# esp32-thing.net
KiCad netlist of a schematic drawn in EAGLE
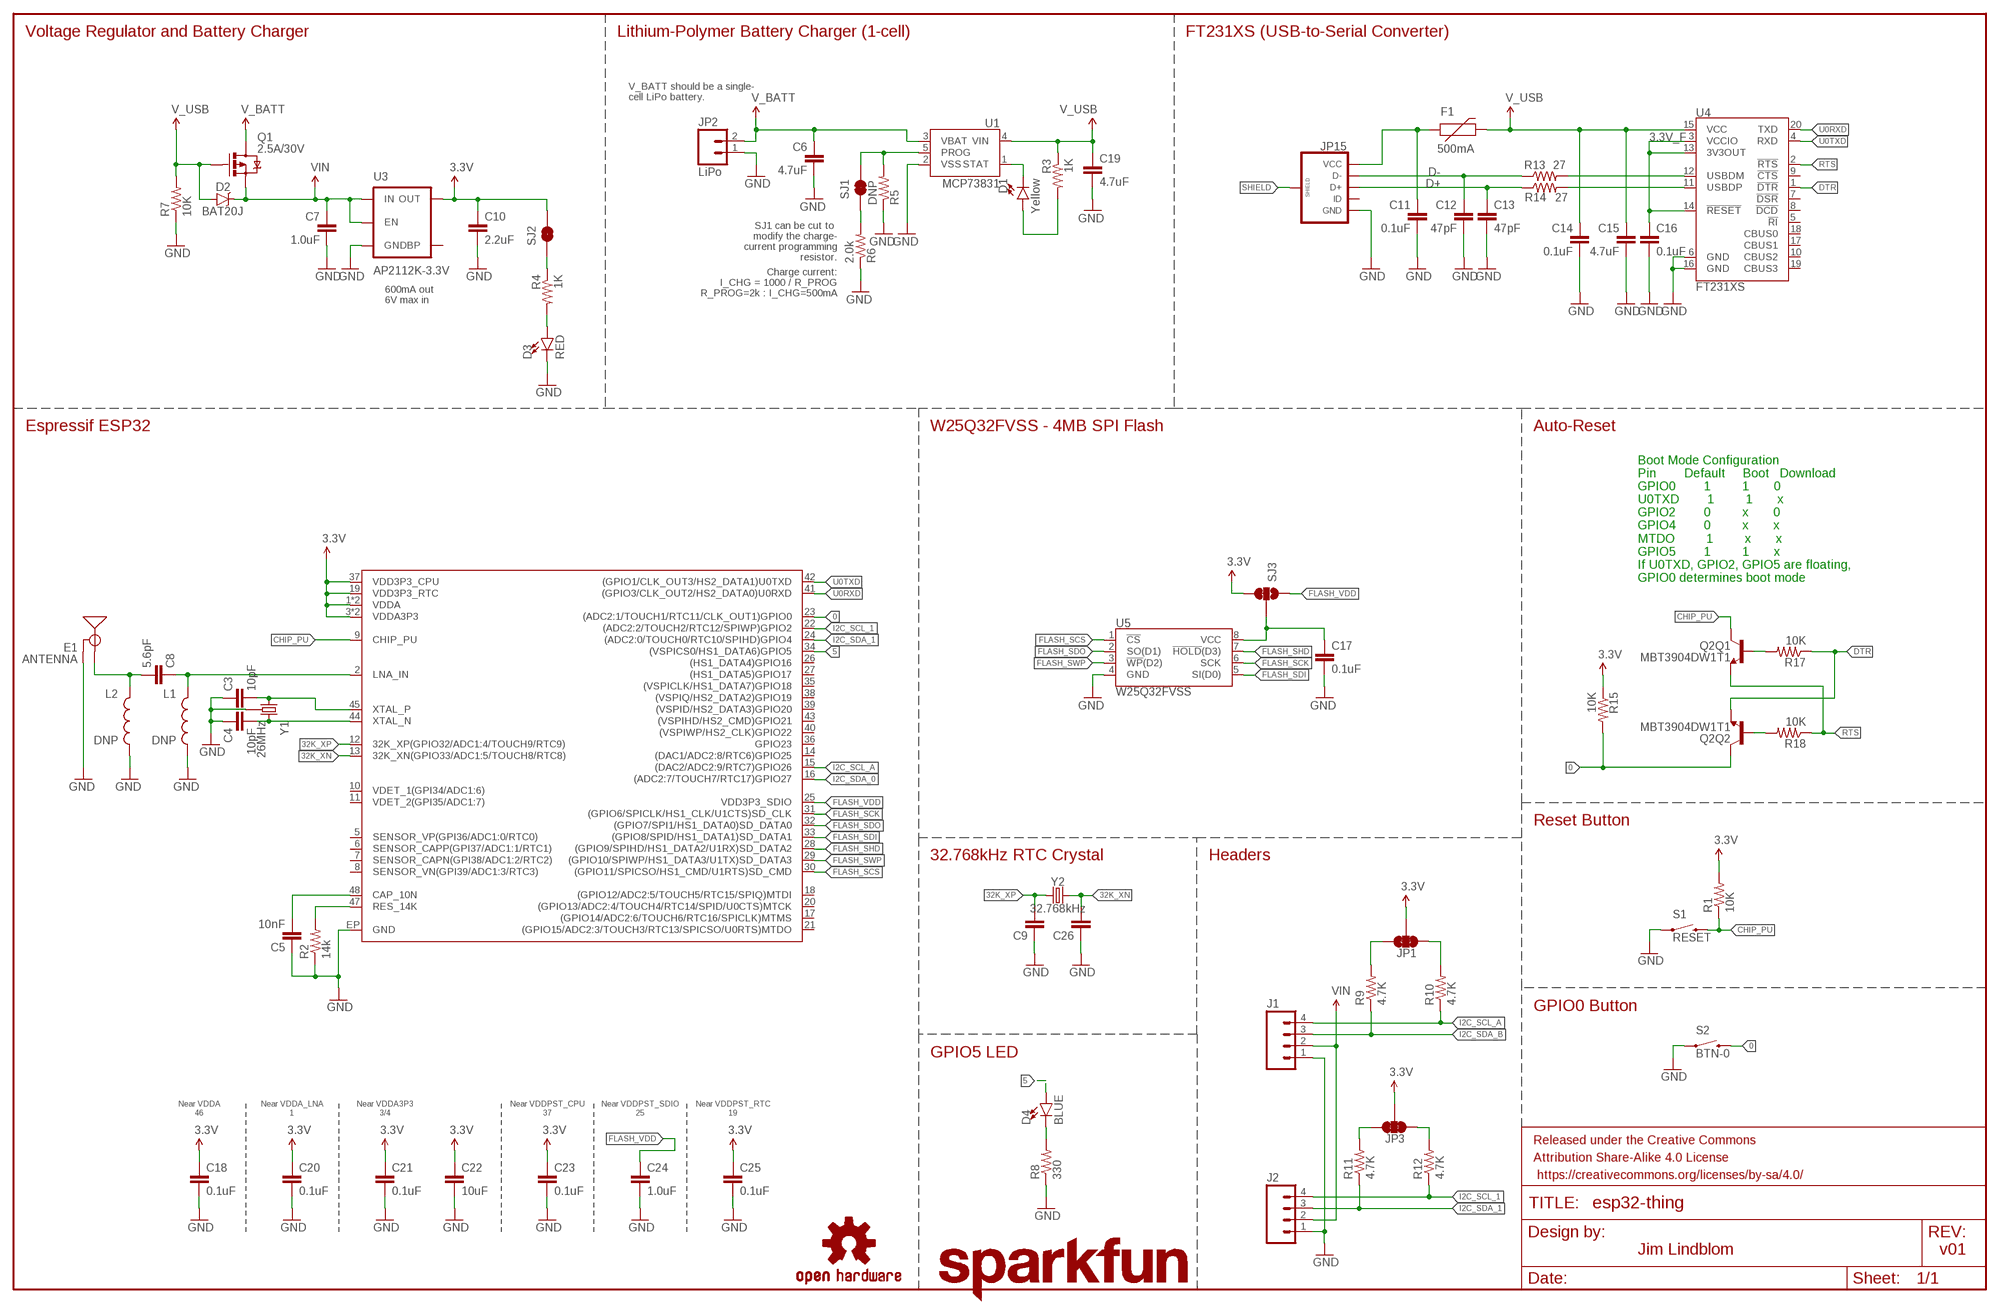
[diagram p0: schematic, sheet 1]

(export (version "E")
  (design (tool "Eeschema 10.0.6"))
  (components
    (comp (ref "C3")
      (value "10pF")
      (footprint "eagle-import:0603-CAP")
      (libsource (lib "eagle-import") (part "10PF-50V-5%(0603)"))
    )
    (comp (ref "C4")
      (value "10pF")
      (footprint "eagle-import:0603-CAP")
      (libsource (lib "eagle-import") (part "10PF-50V-5%(0603)"))
    )
    (comp (ref "C5")
      (value "10nF")
      (footprint "eagle-import:0603-CAP")
      (libsource (lib "eagle-import") (part "10NF/10000PF-50V-10%(0603)"))
    )
    (comp (ref "C6")
      (value "4.7uF")
      (footprint "eagle-import:0603-CAP")
      (libsource (lib "eagle-import") (part "4.7UF-6.3V-10%(0603)0603"))
    )
    (comp (ref "C7")
      (value "1.0uF")
      (footprint "eagle-import:0805-CAP")
      (libsource (lib "eagle-import") (part "1.0UF-25V-+80/-20(0805){dblquote}"))
    )
    (comp (ref "C8")
      (value "5.6pF")
      (footprint "eagle-import:0603-CAP")
      (libsource (lib "eagle-import") (part "CAP0603-CAP"))
    )
    (comp (ref "C9")
      (value "CAP0603-CAP")
      (footprint "eagle-import:0603-CAP")
      (libsource (lib "eagle-import") (part "SparkFun-Passives_CAP0603-CAP"))
    )
    (comp (ref "C10")
      (value "2.2uF")
      (footprint "eagle-import:0603-CAP")
      (libsource (lib "eagle-import") (part "2.2UF-10V-20%(0603)"))
    )
    (comp (ref "C11")
      (value "0.1uF")
      (footprint "eagle-import:0603-CAP")
      (libsource (lib "eagle-import") (part "0.1UF-25V(+80/-20%)(0603)"))
    )
    (comp (ref "C12")
      (value "47pF")
      (footprint "eagle-import:0603-CAP")
      (libsource (lib "eagle-import") (part "47PF-50V-5%(0603)"))
    )
    (comp (ref "C13")
      (value "47pF")
      (footprint "eagle-import:0603-CAP")
      (libsource (lib "eagle-import") (part "47PF-50V-5%(0603)"))
    )
    (comp (ref "C14")
      (value "0.1uF")
      (footprint "eagle-import:0603-CAP")
      (libsource (lib "eagle-import") (part "0.1UF-25V(+80/-20%)(0603)"))
    )
    (comp (ref "C15")
      (value "4.7uF")
      (footprint "eagle-import:0603-CAP")
      (libsource (lib "eagle-import") (part "4.7UF-6.3V-10%(0603)0603"))
    )
    (comp (ref "C16")
      (value "0.1uF")
      (footprint "eagle-import:0603-CAP")
      (libsource (lib "eagle-import") (part "0.1UF-25V(+80/-20%)(0603)"))
    )
    (comp (ref "C17")
      (value "0.1uF")
      (footprint "eagle-import:0603-CAP")
      (libsource (lib "eagle-import") (part "0.1UF-25V(+80/-20%)(0603)"))
    )
    (comp (ref "C18")
      (value "0.1uF")
      (footprint "eagle-import:0603-CAP")
      (libsource (lib "eagle-import") (part "0.1UF-25V(+80/-20%)(0603)"))
    )
    (comp (ref "C19")
      (value "4.7uF")
      (footprint "eagle-import:0603-CAP")
      (libsource (lib "eagle-import") (part "4.7UF-6.3V-10%(0603)0603"))
    )
    (comp (ref "C20")
      (value "0.1uF")
      (footprint "eagle-import:0603-CAP")
      (libsource (lib "eagle-import") (part "0.1UF-25V(+80/-20%)(0603)"))
    )
    (comp (ref "C21")
      (value "0.1uF")
      (footprint "eagle-import:0603-CAP")
      (libsource (lib "eagle-import") (part "0.1UF-25V(+80/-20%)(0603)"))
    )
    (comp (ref "C22")
      (value "10uF")
      (footprint "eagle-import:0603-CAP")
      (libsource (lib "eagle-import") (part "10UF-6.3V-20%(0603)"))
    )
    (comp (ref "C23")
      (value "0.1uF")
      (footprint "eagle-import:0603-CAP")
      (libsource (lib "eagle-import") (part "0.1UF-25V(+80/-20%)(0603)"))
    )
    (comp (ref "C24")
      (value "1.0uF")
      (footprint "eagle-import:0603-CAP")
      (libsource (lib "eagle-import") (part "1.0UF-16V-10%(0603)"))
    )
    (comp (ref "C25")
      (value "0.1uF")
      (footprint "eagle-import:0603-CAP")
      (libsource (lib "eagle-import") (part "0.1UF-25V(+80/-20%)(0603)"))
    )
    (comp (ref "C26")
      (value "CAP0603-CAP")
      (footprint "eagle-import:0603-CAP")
      (libsource (lib "eagle-import") (part "SparkFun-Passives_CAP0603-CAP"))
    )
    (comp (ref "D1")
      (value "Yellow")
      (footprint "eagle-import:LED-0603")
      (libsource (lib "eagle-import") (part "LED-YELLOW0603"))
    )
    (comp (ref "D2")
      (value "BAT20J")
      (footprint "eagle-import:SOD-323")
      (libsource (lib "eagle-import") (part "DIODE-SCHOTTKY-BAT20J"))
    )
    (comp (ref "D3")
      (value "RED")
      (footprint "eagle-import:LED-0603")
      (libsource (lib "eagle-import") (part "LED-RED0603"))
    )
    (comp (ref "D4")
      (value "BLUE")
      (footprint "eagle-import:LED-0603")
      (libsource (lib "eagle-import") (part "LED-BLUE0603"))
    )
    (comp (ref "E1")
      (value "ANTENNA")
      (footprint "eagle-import:TRACE_ANTENNA_2.4GHZ_25.7MM_TUNED")
      (libsource (lib "eagle-import") (part "ANTENNATRACE-TUNED"))
    )
    (comp (ref "F1")
      (value "500mA")
      (footprint "eagle-import:PTC-1206")
      (libsource (lib "eagle-import") (part "PTCSMD"))
    )
    (comp (ref "FRAME1")
      (value "FRAME-LEDGER")
      (footprint "eagle-import:CREATIVE_COMMONS")
      (libsource (lib "eagle-import") (part "FRAME-LEDGER"))
    )
    (comp (ref "J1")
      (value "M04POLAR_LOCK")
      (footprint "eagle-import:MOLEX-1X4_LOCK")
      (libsource (lib "eagle-import") (part "M04POLAR_LOCK"))
    )
    (comp (ref "J2")
      (value "M04POLAR_LOCK")
      (footprint "eagle-import:MOLEX-1X4_LOCK")
      (libsource (lib "eagle-import") (part "M04POLAR_LOCK"))
    )
    (comp (ref "JP1")
      (value "JUMPER-PAD-3-NC_BY_TRACE")
      (footprint "eagle-import:PAD-JUMPER-3-3OF3_NC_BY_TRACE_YES_SILK_FULL_BOX")
      (libsource (lib "eagle-import") (part "JUMPER-PAD-3-NC_BY_TRACE"))
    )
    (comp (ref "JP2")
      (value "LiPo")
      (footprint "eagle-import:JST-2-PTH")
      (libsource (lib "eagle-import") (part "M02JST-PTH-2"))
    )
    (comp (ref "JP3")
      (value "JUMPER-PAD-3-NC_BY_TRACE")
      (footprint "eagle-import:PAD-JUMPER-3-3OF3_NC_BY_TRACE_YES_SILK_FULL_BOX")
      (libsource (lib "eagle-import") (part "JUMPER-PAD-3-NC_BY_TRACE"))
    )
    (comp (ref "JP15")
      (value "USB_MICROB_PLUGCONN-11752")
      (footprint "eagle-import:USB-B-MICRO-SMD_V03")
      (libsource (lib "eagle-import") (part "USB_MICROB_PLUGCONN-11752"))
    )
    (comp (ref "L1")
      (value "DNP")
      (footprint "eagle-import:0603")
      (libsource (lib "eagle-import") (part "INDUCTOR0603"))
    )
    (comp (ref "L2")
      (value "DNP")
      (footprint "eagle-import:0603")
      (libsource (lib "eagle-import") (part "INDUCTOR0603"))
    )
    (comp (ref "LOGO1")
      (value "SFE_LOGO_NAME.2_INCH")
      (footprint "eagle-import:SFE_LOGO_NAME_.2")
      (libsource (lib "eagle-import") (part "SFE_LOGO_NAME.2_INCH"))
    )
    (comp (ref "LOGO2")
      (value "OSHW-LOGOMINI")
      (footprint "eagle-import:OSHW-LOGO-MINI")
      (libsource (lib "eagle-import") (part "OSHW-LOGOMINI"))
    )
    (comp (ref "Q1")
      (value "2.5A/30V")
      (footprint "eagle-import:SOT23-3")
      (libsource (lib "eagle-import") (part "MOSFET-PCHANNELDMG2307L"))
    )
    (comp (ref "Q2")
      (value "MBT3904DW1T1")
      (footprint "eagle-import:SC70-6")
      (libsource (lib "eagle-import") (part "MBT3904DW1T1"))
    )
    (comp (ref "R1")
      (value "10K")
      (footprint "eagle-import:0603-RES")
      (libsource (lib "eagle-import") (part "10KOHM-1/10W-1%(0603)0603"))
    )
    (comp (ref "R2")
      (value "14k")
      (footprint "eagle-import:0603-RES")
      (libsource (lib "eagle-import") (part "RESISTOR0603-RES"))
    )
    (comp (ref "R3")
      (value "1K")
      (footprint "eagle-import:0603-RES")
      (libsource (lib "eagle-import") (part "1KOHM-1/10W-1%(0603)"))
    )
    (comp (ref "R4")
      (value "1K")
      (footprint "eagle-import:0603-RES")
      (libsource (lib "eagle-import") (part "1KOHM-1/10W-1%(0603)"))
    )
    (comp (ref "R5")
      (value "DNP")
      (footprint "eagle-import:1_6W-RES")
      (libsource (lib "eagle-import") (part "RESISTORPTH-1/6W"))
    )
    (comp (ref "R6")
      (value "2.0k")
      (footprint "eagle-import:0603-RES")
      (libsource (lib "eagle-import") (part "2.0KOHM1/10W5%(0603)"))
    )
    (comp (ref "R7")
      (value "10K")
      (footprint "eagle-import:0603-RES@1")
      (libsource (lib "eagle-import") (part "10KOHM1/10W1%(0603)0603"))
    )
    (comp (ref "R8")
      (value "330")
      (footprint "eagle-import:0603-RES")
      (libsource (lib "eagle-import") (part "330OHM1/10W1%(0603)"))
    )
    (comp (ref "R9")
      (value "4.7K")
      (footprint "eagle-import:0603-RES")
      (libsource (lib "eagle-import") (part "4.7KOHM-1/10W-1%(0603)"))
    )
    (comp (ref "R10")
      (value "4.7K")
      (footprint "eagle-import:0603-RES")
      (libsource (lib "eagle-import") (part "4.7KOHM-1/10W-1%(0603)"))
    )
    (comp (ref "R11")
      (value "4.7K")
      (footprint "eagle-import:0603-RES")
      (libsource (lib "eagle-import") (part "4.7KOHM-1/10W-1%(0603)"))
    )
    (comp (ref "R12")
      (value "4.7K")
      (footprint "eagle-import:0603-RES")
      (libsource (lib "eagle-import") (part "4.7KOHM-1/10W-1%(0603)"))
    )
    (comp (ref "R13")
      (value "27")
      (footprint "eagle-import:0603-RES")
      (libsource (lib "eagle-import") (part "27OHM1/10W1%(0603)0603-RES"))
    )
    (comp (ref "R14")
      (value "27")
      (footprint "eagle-import:0603-RES")
      (libsource (lib "eagle-import") (part "27OHM1/10W1%(0603)0603-RES"))
    )
    (comp (ref "R15")
      (value "10K")
      (footprint "eagle-import:0603-RES@1")
      (libsource (lib "eagle-import") (part "10KOHM1/10W1%(0603)0603"))
    )
    (comp (ref "R17")
      (value "10K")
      (footprint "eagle-import:0603-RES@1")
      (libsource (lib "eagle-import") (part "10KOHM1/10W1%(0603)0603"))
    )
    (comp (ref "R18")
      (value "10K")
      (footprint "eagle-import:0603-RES@1")
      (libsource (lib "eagle-import") (part "10KOHM1/10W1%(0603)0603"))
    )
    (comp (ref "S1")
      (value "RESET")
      (footprint "eagle-import:TACTILE_SWITCH_SMD_4.6X2.8MM")
      (libsource (lib "eagle-import") (part "SWITCH-MOMENTARY-2SMD-4.6X2.8MM"))
    )
    (comp (ref "S2")
      (value "BTN-0")
      (footprint "eagle-import:TACTILE_SWITCH_SMD_4.6X2.8MM")
      (libsource (lib "eagle-import") (part "SWITCH-MOMENTARY-2SMD-4.6X2.8MM"))
    )
    (comp (ref "SJ1")
      (value "JUMPER-PAD-2-NC_BY_TRACE")
      (footprint "eagle-import:PAD-JUMPER-2-NC_BY_TRACE_YES_SILK")
      (libsource (lib "eagle-import") (part "JUMPER-PAD-2-NC_BY_TRACE"))
    )
    (comp (ref "SJ2")
      (value "JUMPER-PAD-2-NC_BY_TRACE")
      (footprint "eagle-import:PAD-JUMPER-2-NC_BY_TRACE_YES_SILK")
      (libsource (lib "eagle-import") (part "JUMPER-PAD-2-NC_BY_TRACE"))
    )
    (comp (ref "SJ3")
      (value "JUMPER-PAD-3-2OF3_NC_BY_TRACE_SMALL")
      (footprint "eagle-import:PAD-JUMPER-3-2OF3_NC_BY_TRACE_YES_SILK_FULL_BOX")
      (libsource (lib "eagle-import") (part "JUMPER-PAD-3-2OF3_NC_BY_TRACE_SMALL"))
    )
    (comp (ref "U$1")
      (value "ESP32")
      (footprint "eagle-import:QFN48-0.4MM")
      (libsource (lib "eagle-import") (part "ESP32"))
    )
    (comp (ref "U1")
      (value "MCP73831")
      (footprint "eagle-import:SOT23-5")
      (libsource (lib "eagle-import") (part "MCP73831"))
    )
    (comp (ref "U3")
      (value "AP2112K-3.3V")
      (footprint "eagle-import:SOT23-5")
      (libsource (lib "eagle-import") (part "V_REG_LDOSMD"))
    )
    (comp (ref "U4")
      (value "FT231XS")
      (footprint "eagle-import:SSOP20_L")
      (libsource (lib "eagle-import") (part "FT231XS"))
    )
    (comp (ref "U5")
      (value "W25Q32FVSS")
      (footprint "eagle-import:SOIC-8")
      (libsource (lib "eagle-import") (part "W25Q32FVSS"))
    )
    (comp (ref "Y1")
      (value "26MHz")
      (footprint "eagle-import:CRYSTAL-SMD-3.2X2.5")
      (libsource (lib "eagle-import") (part "CRYSTAL-GROUNDED3.2X2.5"))
    )
    (comp (ref "Y2")
      (value "32.768kHz")
      (footprint "eagle-import:CRYSTAL-SMD-3.2X1.5MM")
      (libsource (lib "eagle-import") (part "CRYSTAL-32.768KHZSMD-3.2X1.5"))
    )
  )
  (nets
    (net (code "1") (name "/3.3V_F") (class "Default")
      (node (ref "C16") (pin "1") (pinfunction "1_1") (pintype "passive"))
      (node (ref "U4") (pin "13") (pinfunction "3V3OUT_13") (pintype "bidirectional"))
      (node (ref "U4") (pin "14") (pinfunction "~{RESET}_14") (pintype "bidirectional"))
      (node (ref "U4") (pin "3") (pinfunction "VCCIO_3") (pintype "bidirectional"))
    )
    (net (code "2") (name "/D+") (class "Default")
      (node (ref "C13") (pin "1") (pinfunction "1_1") (pintype "passive"))
      (node (ref "JP15") (pin "D+") (pinfunction "D+_D+") (pintype "bidirectional"))
      (node (ref "R14") (pin "1") (pinfunction "1_1") (pintype "passive"))
    )
    (net (code "3") (name "/D-") (class "Default")
      (node (ref "C12") (pin "1") (pinfunction "1_1") (pintype "passive"))
      (node (ref "JP15") (pin "D-") (pinfunction "D-_D-") (pintype "bidirectional"))
      (node (ref "R13") (pin "1") (pinfunction "1_1") (pintype "passive"))
    )
    (net (code "4") (name "0") (class "Default")
      (node (ref "Q2") (pin "6") (pinfunction "C_6") (pintype "passive"))
      (node (ref "R15") (pin "2") (pinfunction "2_2") (pintype "passive"))
      (node (ref "S2") (pin "3") (pinfunction "2_3") (pintype "passive"))
      (node (ref "S2") (pin "4") (pinfunction "2_4") (pintype "passive"))
      (node (ref "U$1") (pin "23") (pinfunction "(ADC2:1/TOUCH1/RTC11/CLK_OUT1)GPIO0_23") (pintype "bidirectional"))
    )
    (net (code "5") (name "3.3V") (class "Default")
      (node (ref "C10") (pin "1") (pinfunction "1_1") (pintype "passive"))
      (node (ref "C18") (pin "1") (pinfunction "1_1") (pintype "passive"))
      (node (ref "C20") (pin "1") (pinfunction "1_1") (pintype "passive"))
      (node (ref "C21") (pin "1") (pinfunction "1_1") (pintype "passive"))
      (node (ref "C22") (pin "1") (pinfunction "1_1") (pintype "passive"))
      (node (ref "C23") (pin "1") (pinfunction "1_1") (pintype "passive"))
      (node (ref "C25") (pin "1") (pinfunction "1_1") (pintype "passive"))
      (node (ref "JP1") (pin "2") (pinfunction "2_2") (pintype "passive"))
      (node (ref "JP3") (pin "2") (pinfunction "2_2") (pintype "passive"))
      (node (ref "R1") (pin "2") (pinfunction "2_2") (pintype "passive"))
      (node (ref "R15") (pin "1") (pinfunction "1_1") (pintype "passive"))
      (node (ref "SJ2") (pin "2") (pinfunction "2_2") (pintype "passive"))
      (node (ref "SJ3") (pin "3") (pinfunction "3_3") (pintype "passive"))
      (node (ref "U$1") (pin "1") (pinfunction "VDDA_1") (pintype "bidirectional"))
      (node (ref "U$1") (pin "19") (pinfunction "VDD3P3_RTC_19") (pintype "bidirectional"))
      (node (ref "U$1") (pin "3") (pinfunction "VDDA3P3_3") (pintype "bidirectional"))
      (node (ref "U$1") (pin "37") (pinfunction "VDD3P3_CPU_37") (pintype "bidirectional"))
      (node (ref "U$1") (pin "4") (pinfunction "VDDA3P3_4") (pintype "bidirectional"))
      (node (ref "U$1") (pin "46") (pinfunction "VDDA_46") (pintype "bidirectional"))
      (node (ref "U3") (pin "5") (pinfunction "OUT_5") (pintype "passive"))
    )
    (net (code "6") (name "5") (class "Default")
      (node (ref "D4") (pin "A") (pinfunction "A_A") (pintype "passive"))
      (node (ref "U$1") (pin "34") (pinfunction "(VSPICS0/HS1_DATA6)GPIO5_34") (pintype "bidirectional"))
    )
    (net (code "7") (name "32K_XN") (class "Default")
      (node (ref "C26") (pin "2") (pinfunction "2_2") (pintype "passive"))
      (node (ref "U$1") (pin "13") (pinfunction "32K_XN(GPIO33/ADC1:5/TOUCH8/RTC8)_13") (pintype "bidirectional"))
      (node (ref "Y2") (pin "P$2") (pinfunction "2_P$2") (pintype "passive"))
    )
    (net (code "8") (name "32K_XP") (class "Default")
      (node (ref "C9") (pin "2") (pinfunction "2_2") (pintype "passive"))
      (node (ref "U$1") (pin "12") (pinfunction "32K_XP(GPIO32/ADC1:4/TOUCH9/RTC9)_12") (pintype "bidirectional"))
      (node (ref "Y2") (pin "P$1") (pinfunction "1_P$1") (pintype "passive"))
    )
    (net (code "9") (name "CHIP_PU") (class "Default")
      (node (ref "Q2") (pin "3") (pinfunction "C_3") (pintype "passive"))
      (node (ref "R1") (pin "1") (pinfunction "1_1") (pintype "passive"))
      (node (ref "S1") (pin "3") (pinfunction "2_3") (pintype "passive"))
      (node (ref "S1") (pin "4") (pinfunction "2_4") (pintype "passive"))
      (node (ref "U$1") (pin "9") (pinfunction "CHIP_PU_9") (pintype "bidirectional"))
    )
    (net (code "10") (name "DTR") (class "Default")
      (node (ref "Q2") (pin "1") (pinfunction "E_1") (pintype "passive"))
      (node (ref "R17") (pin "1") (pinfunction "1_1") (pintype "passive"))
      (node (ref "U4") (pin "1") (pinfunction "~{DTR}_1") (pintype "bidirectional"))
    )
    (net (code "11") (name "FLASH_SCK") (class "Default")
      (node (ref "U$1") (pin "31") (pinfunction "(GPIO6/SPICLK/HS1_CLK/U1CTS)SD_CLK_31") (pintype "bidirectional"))
      (node (ref "U5") (pin "6") (pinfunction "SCK_6") (pintype "bidirectional"))
    )
    (net (code "12") (name "FLASH_SCS") (class "Default")
      (node (ref "U$1") (pin "30") (pinfunction "(GPIO11/SPICSO/HS1_CMD/U1RTS)SD_CMD_30") (pintype "bidirectional"))
      (node (ref "U5") (pin "1") (pinfunction "~{CS}_1") (pintype "bidirectional"))
    )
    (net (code "13") (name "FLASH_SDI") (class "Default")
      (node (ref "U$1") (pin "33") (pinfunction "(GPIO8/SPID/HS1_DATA1)SD_DATA1_33") (pintype "bidirectional"))
      (node (ref "U5") (pin "5") (pinfunction "SI(D0)_5") (pintype "bidirectional"))
    )
    (net (code "14") (name "FLASH_SDO") (class "Default")
      (node (ref "U$1") (pin "32") (pinfunction "(GPIO7/SPI1/HS1_DATA0)SD_DATA0_32") (pintype "bidirectional"))
      (node (ref "U5") (pin "2") (pinfunction "SO(D1)_2") (pintype "bidirectional"))
    )
    (net (code "15") (name "FLASH_SHD") (class "Default")
      (node (ref "U$1") (pin "28") (pinfunction "(GPIO9/SPIHD/HS1_DATA2/U1RX)SD_DATA2_28") (pintype "bidirectional"))
      (node (ref "U5") (pin "7") (pinfunction "~{HOLD}(D3)_7") (pintype "bidirectional"))
    )
    (net (code "16") (name "FLASH_SWP") (class "Default")
      (node (ref "U$1") (pin "29") (pinfunction "(GPIO10/SPIWP/HS1_DATA3/U1TX)SD_DATA3_29") (pintype "bidirectional"))
      (node (ref "U5") (pin "3") (pinfunction "~{WP}(D2)_3") (pintype "bidirectional"))
    )
    (net (code "17") (name "FLASH_VDD") (class "Default")
      (node (ref "C24") (pin "1") (pinfunction "1_1") (pintype "passive"))
      (node (ref "SJ3") (pin "1") (pinfunction "1_1") (pintype "passive"))
      (node (ref "U$1") (pin "25") (pinfunction "VDD3P3_SDIO_25") (pintype "bidirectional"))
    )
    (net (code "18") (name "GND") (class "Default")
      (node (ref "C10") (pin "2") (pinfunction "2_2") (pintype "passive"))
      (node (ref "C11") (pin "2") (pinfunction "2_2") (pintype "passive"))
      (node (ref "C12") (pin "2") (pinfunction "2_2") (pintype "passive"))
      (node (ref "C13") (pin "2") (pinfunction "2_2") (pintype "passive"))
      (node (ref "C14") (pin "2") (pinfunction "2_2") (pintype "passive"))
      (node (ref "C15") (pin "2") (pinfunction "2_2") (pintype "passive"))
      (node (ref "C16") (pin "2") (pinfunction "2_2") (pintype "passive"))
      (node (ref "C17") (pin "2") (pinfunction "2_2") (pintype "passive"))
      (node (ref "C18") (pin "2") (pinfunction "2_2") (pintype "passive"))
      (node (ref "C19") (pin "2") (pinfunction "2_2") (pintype "passive"))
      (node (ref "C20") (pin "2") (pinfunction "2_2") (pintype "passive"))
      (node (ref "C21") (pin "2") (pinfunction "2_2") (pintype "passive"))
      (node (ref "C22") (pin "2") (pinfunction "2_2") (pintype "passive"))
      (node (ref "C23") (pin "2") (pinfunction "2_2") (pintype "passive"))
      (node (ref "C24") (pin "2") (pinfunction "2_2") (pintype "passive"))
      (node (ref "C25") (pin "2") (pinfunction "2_2") (pintype "passive"))
      (node (ref "C26") (pin "1") (pinfunction "1_1") (pintype "passive"))
      (node (ref "C3") (pin "1") (pinfunction "1_1") (pintype "passive"))
      (node (ref "C4") (pin "1") (pinfunction "1_1") (pintype "passive"))
      (node (ref "C5") (pin "1") (pinfunction "1_1") (pintype "passive"))
      (node (ref "C6") (pin "2") (pinfunction "2_2") (pintype "passive"))
      (node (ref "C7") (pin "2") (pinfunction "2_2") (pintype "passive"))
      (node (ref "C9") (pin "1") (pinfunction "1_1") (pintype "passive"))
      (node (ref "D3") (pin "C") (pinfunction "C_C") (pintype "passive"))
      (node (ref "E1") (pin "GND") (pinfunction "GND_GND") (pintype "bidirectional"))
      (node (ref "E1") (pin "GND2") (pinfunction "GND_GND2") (pintype "bidirectional"))
      (node (ref "J1") (pin "1") (pinfunction "1_1") (pintype "passive"))
      (node (ref "J2") (pin "1") (pinfunction "1_1") (pintype "passive"))
      (node (ref "JP15") (pin "GND") (pinfunction "GND_GND") (pintype "bidirectional"))
      (node (ref "JP2") (pin "1") (pinfunction "1_1") (pintype "passive"))
      (node (ref "L1") (pin "2") (pinfunction "2_2") (pintype "passive"))
      (node (ref "L2") (pin "2") (pinfunction "2_2") (pintype "passive"))
      (node (ref "R2") (pin "1") (pinfunction "1_1") (pintype "passive"))
      (node (ref "R5") (pin "1") (pinfunction "1_1") (pintype "passive"))
      (node (ref "R6") (pin "1") (pinfunction "1_1") (pintype "passive"))
      (node (ref "R7") (pin "1") (pinfunction "1_1") (pintype "passive"))
      (node (ref "R8") (pin "1") (pinfunction "1_1") (pintype "passive"))
      (node (ref "S1") (pin "1") (pinfunction "1_1") (pintype "passive"))
      (node (ref "S1") (pin "2") (pinfunction "1_2") (pintype "passive"))
      (node (ref "S2") (pin "1") (pinfunction "1_1") (pintype "passive"))
      (node (ref "S2") (pin "2") (pinfunction "1_2") (pintype "passive"))
      (node (ref "U$1") (pin "EP") (pinfunction "GND_EP") (pintype "bidirectional"))
      (node (ref "U1") (pin "2") (pinfunction "VSS_2") (pintype "power_in"))
      (node (ref "U3") (pin "2") (pinfunction "GND_2") (pintype "input"))
      (node (ref "U4") (pin "16") (pinfunction "GND_16") (pintype "bidirectional"))
      (node (ref "U4") (pin "6") (pinfunction "GND_6") (pintype "bidirectional"))
      (node (ref "U5") (pin "4") (pinfunction "GND_4") (pintype "bidirectional"))
      (node (ref "Y1") (pin "2") (pinfunction "GND_2") (pintype "passive"))
      (node (ref "Y1") (pin "4") (pinfunction "GND_4") (pintype "passive"))
    )
    (net (code "19") (name "I2C_SCL_1") (class "Default")
      (node (ref "J2") (pin "4") (pinfunction "4_4") (pintype "passive"))
      (node (ref "R12") (pin "1") (pinfunction "1_1") (pintype "passive"))
      (node (ref "U$1") (pin "22") (pinfunction "(ADC2:2/TOUCH2/RTC12/SPIWP)GPIO2_22") (pintype "bidirectional"))
    )
    (net (code "20") (name "I2C_SCL_A") (class "Default")
      (node (ref "J1") (pin "4") (pinfunction "4_4") (pintype "passive"))
      (node (ref "R10") (pin "1") (pinfunction "1_1") (pintype "passive"))
      (node (ref "U$1") (pin "15") (pinfunction "(DAC2/ADC2:9/RTC7)GPIO26_15") (pintype "bidirectional"))
    )
    (net (code "21") (name "I2C_SDA_0") (class "Default")
      (node (ref "U$1") (pin "16") (pinfunction "(ADC2:7/TOUCH7/RTC17)GPIO27_16") (pintype "bidirectional"))
    )
    (net (code "22") (name "I2C_SDA_1") (class "Default")
      (node (ref "J2") (pin "3") (pinfunction "3_3") (pintype "passive"))
      (node (ref "R11") (pin "1") (pinfunction "1_1") (pintype "passive"))
      (node (ref "U$1") (pin "24") (pinfunction "(ADC2:0/TOUCH0/RTC10/SPIHD)GPIO4_24") (pintype "bidirectional"))
    )
    (net (code "23") (name "I2C_SDA_B") (class "Default")
      (node (ref "J1") (pin "3") (pinfunction "3_3") (pintype "passive"))
      (node (ref "R9") (pin "1") (pinfunction "1_1") (pintype "passive"))
    )
    (net (code "24") (name "Net-(D1-PadA)") (class "Default")
      (node (ref "D1") (pin "A") (pinfunction "A_A") (pintype "passive"))
      (node (ref "R3") (pin "2") (pinfunction "2_2") (pintype "passive"))
    )
    (net (code "25") (name "Net-(D3-PadA)") (class "Default")
      (node (ref "D3") (pin "A") (pinfunction "A_A") (pintype "passive"))
      (node (ref "R4") (pin "2") (pinfunction "2_2") (pintype "passive"))
    )
    (net (code "26") (name "Net-(D4-PadC)") (class "Default")
      (node (ref "D4") (pin "C") (pinfunction "C_C") (pintype "passive"))
      (node (ref "R8") (pin "2") (pinfunction "2_2") (pintype "passive"))
    )
    (net (code "27") (name "Net-(E1-SIGNAL)") (class "Default")
      (node (ref "C8") (pin "2") (pinfunction "2_2") (pintype "passive"))
      (node (ref "E1") (pin "ANT") (pinfunction "SIGNAL_ANT") (pintype "bidirectional"))
      (node (ref "L2") (pin "1") (pinfunction "1_1") (pintype "passive"))
    )
    (net (code "28") (name "Net-(JP1-Pad1)") (class "Default")
      (node (ref "JP1") (pin "1") (pinfunction "1_1") (pintype "passive"))
      (node (ref "R10") (pin "2") (pinfunction "2_2") (pintype "passive"))
    )
    (net (code "29") (name "Net-(JP1-Pad3)") (class "Default")
      (node (ref "JP1") (pin "3") (pinfunction "3_3") (pintype "passive"))
      (node (ref "R9") (pin "2") (pinfunction "2_2") (pintype "passive"))
    )
    (net (code "30") (name "Net-(JP3-Pad1)") (class "Default")
      (node (ref "JP3") (pin "1") (pinfunction "1_1") (pintype "passive"))
      (node (ref "R12") (pin "2") (pinfunction "2_2") (pintype "passive"))
    )
    (net (code "31") (name "Net-(JP3-Pad3)") (class "Default")
      (node (ref "JP3") (pin "3") (pinfunction "3_3") (pintype "passive"))
      (node (ref "R11") (pin "2") (pinfunction "2_2") (pintype "passive"))
    )
    (net (code "32") (name "Net-(JP15-VCC)") (class "Default")
      (node (ref "C11") (pin "1") (pinfunction "1_1") (pintype "passive"))
      (node (ref "F1") (pin "1") (pinfunction "1_1") (pintype "bidirectional"))
      (node (ref "JP15") (pin "VBUS") (pinfunction "VCC_VBUS") (pintype "bidirectional"))
    )
    (net (code "33") (name "Net-(Q2A-B)") (class "Default")
      (node (ref "Q2") (pin "5") (pinfunction "B_5") (pintype "passive"))
      (node (ref "R17") (pin "2") (pinfunction "2_2") (pintype "passive"))
    )
    (net (code "34") (name "Net-(Q2B-B)") (class "Default")
      (node (ref "Q2") (pin "2") (pinfunction "B_2") (pintype "passive"))
      (node (ref "R18") (pin "2") (pinfunction "2_2") (pintype "passive"))
    )
    (net (code "35") (name "Net-(R4-Pad1)") (class "Default")
      (node (ref "R4") (pin "1") (pinfunction "1_1") (pintype "passive"))
      (node (ref "SJ2") (pin "1") (pinfunction "1_1") (pintype "passive"))
    )
    (net (code "36") (name "Net-(R6-Pad2)") (class "Default")
      (node (ref "R6") (pin "2") (pinfunction "2_2") (pintype "passive"))
      (node (ref "SJ1") (pin "1") (pinfunction "1_1") (pintype "passive"))
    )
    (net (code "37") (name "Net-(U$1-CAP_10N)") (class "Default")
      (node (ref "C5") (pin "2") (pinfunction "2_2") (pintype "passive"))
      (node (ref "U$1") (pin "48") (pinfunction "CAP_10N_48") (pintype "bidirectional"))
    )
    (net (code "38") (name "Net-(U$1-LNA_IN)") (class "Default")
      (node (ref "C8") (pin "1") (pinfunction "1_1") (pintype "passive"))
      (node (ref "L1") (pin "1") (pinfunction "1_1") (pintype "passive"))
      (node (ref "U$1") (pin "2") (pinfunction "LNA_IN_2") (pintype "bidirectional"))
    )
    (net (code "39") (name "Net-(U$1-RES_14K)") (class "Default")
      (node (ref "R2") (pin "2") (pinfunction "2_2") (pintype "passive"))
      (node (ref "U$1") (pin "47") (pinfunction "RES_14K_47") (pintype "bidirectional"))
    )
    (net (code "40") (name "Net-(U$1-XTAL_N)") (class "Default")
      (node (ref "C4") (pin "2") (pinfunction "2_2") (pintype "passive"))
      (node (ref "U$1") (pin "44") (pinfunction "XTAL_N_44") (pintype "bidirectional"))
      (node (ref "Y1") (pin "3") (pinfunction "2_3") (pintype "passive"))
    )
    (net (code "41") (name "Net-(U$1-XTAL_P)") (class "Default")
      (node (ref "C3") (pin "2") (pinfunction "2_2") (pintype "passive"))
      (node (ref "U$1") (pin "45") (pinfunction "XTAL_P_45") (pintype "bidirectional"))
      (node (ref "Y1") (pin "1") (pinfunction "1_1") (pintype "passive"))
    )
    (net (code "42") (name "Net-(U1-PROG)") (class "Default")
      (node (ref "R5") (pin "2") (pinfunction "2_2") (pintype "passive"))
      (node (ref "SJ1") (pin "2") (pinfunction "2_2") (pintype "passive"))
      (node (ref "U1") (pin "5") (pinfunction "PROG_5") (pintype "input"))
    )
    (net (code "43") (name "Net-(U1-STAT)") (class "Default")
      (node (ref "D1") (pin "C") (pinfunction "C_C") (pintype "passive"))
      (node (ref "U1") (pin "1") (pinfunction "STAT_1") (pintype "output"))
    )
    (net (code "44") (name "Net-(U4-USBDM)") (class "Default")
      (node (ref "R13") (pin "2") (pinfunction "2_2") (pintype "passive"))
      (node (ref "U4") (pin "12") (pinfunction "USBDM_12") (pintype "bidirectional"))
    )
    (net (code "45") (name "Net-(U4-USBDP)") (class "Default")
      (node (ref "R14") (pin "2") (pinfunction "2_2") (pintype "passive"))
      (node (ref "U4") (pin "11") (pinfunction "USBDP_11") (pintype "bidirectional"))
    )
    (net (code "46") (name "Net-(U5-VCC)") (class "Default")
      (node (ref "C17") (pin "1") (pinfunction "1_1") (pintype "passive"))
      (node (ref "SJ3") (pin "2") (pinfunction "2_2") (pintype "passive"))
      (node (ref "U5") (pin "8") (pinfunction "VCC_8") (pintype "bidirectional"))
    )
    (net (code "47") (name "RTS") (class "Default")
      (node (ref "Q2") (pin "4") (pinfunction "E_4") (pintype "passive"))
      (node (ref "R18") (pin "1") (pinfunction "1_1") (pintype "passive"))
      (node (ref "U4") (pin "2") (pinfunction "~{RTS}_2") (pintype "bidirectional"))
    )
    (net (code "48") (name "SHIELD") (class "Default")
      (node (ref "JP15") (pin "SHIELD1") (pinfunction "SHIELD_SHIELD1") (pintype "bidirectional"))
      (node (ref "JP15") (pin "SHIELD2") (pinfunction "SHIELD_SHIELD2") (pintype "bidirectional"))
      (node (ref "JP15") (pin "SHIELD3") (pinfunction "SHIELD_SHIELD3") (pintype "bidirectional"))
    )
    (net (code "49") (name "U0RXD") (class "Default")
      (node (ref "U$1") (pin "41") (pinfunction "(GPIO3/CLK_OUT2/HS2_DATA0)U0RXD_41") (pintype "bidirectional"))
      (node (ref "U4") (pin "20") (pinfunction "TXD_20") (pintype "bidirectional"))
    )
    (net (code "50") (name "U0TXD") (class "Default")
      (node (ref "U$1") (pin "42") (pinfunction "(GPIO1/CLK_OUT3/HS2_DATA1)U0TXD_42") (pintype "bidirectional"))
      (node (ref "U4") (pin "4") (pinfunction "RXD_4") (pintype "bidirectional"))
    )
    (net (code "51") (name "VIN") (class "Default")
      (node (ref "C7") (pin "1") (pinfunction "1_1") (pintype "passive"))
      (node (ref "D2") (pin "C") (pinfunction "C_C") (pintype "passive"))
      (node (ref "J1") (pin "2") (pinfunction "2_2") (pintype "passive"))
      (node (ref "J2") (pin "2") (pinfunction "2_2") (pintype "passive"))
      (node (ref "Q1") (pin "2") (pinfunction "S_2") (pintype "passive"))
      (node (ref "U3") (pin "1") (pinfunction "IN_1") (pintype "input"))
      (node (ref "U3") (pin "3") (pinfunction "EN_3") (pintype "input"))
    )
    (net (code "52") (name "V_BATT") (class "Default")
      (node (ref "C6") (pin "1") (pinfunction "1_1") (pintype "passive"))
      (node (ref "JP2") (pin "2") (pinfunction "2_2") (pintype "passive"))
      (node (ref "Q1") (pin "3") (pinfunction "D_3") (pintype "passive"))
      (node (ref "U1") (pin "3") (pinfunction "VBAT_3") (pintype "power_in"))
    )
    (net (code "53") (name "V_USB") (class "Default")
      (node (ref "C14") (pin "1") (pinfunction "1_1") (pintype "passive"))
      (node (ref "C15") (pin "1") (pinfunction "1_1") (pintype "passive"))
      (node (ref "C19") (pin "1") (pinfunction "1_1") (pintype "passive"))
      (node (ref "D2") (pin "A") (pinfunction "A_A") (pintype "passive"))
      (node (ref "F1") (pin "2") (pinfunction "2_2") (pintype "bidirectional"))
      (node (ref "Q1") (pin "1") (pinfunction "G_1") (pintype "passive"))
      (node (ref "R3") (pin "1") (pinfunction "1_1") (pintype "passive"))
      (node (ref "R7") (pin "2") (pinfunction "2_2") (pintype "passive"))
      (node (ref "U1") (pin "4") (pinfunction "VIN_4") (pintype "power_in"))
      (node (ref "U4") (pin "15") (pinfunction "VCC_15") (pintype "bidirectional"))
    )
    (net (code "54") (name "unconnected-(JP15-PadID)") (class "Default")
      (node (ref "JP15") (pin "ID") (pinfunction "ID_ID") (pintype "bidirectional"))
    )
    (net (code "55") (name "unconnected-(U$1-(DAC1{slash}ADC2:8{slash}RTC6)GPIO25-Pad14)") (class "Default")
      (node (ref "U$1") (pin "14") (pinfunction "(DAC1/ADC2:8/RTC6)GPIO25_14") (pintype "bidirectional"))
    )
    (net (code "56") (name "unconnected-(U$1-(GPIO12{slash}ADC2:5{slash}TOUCH5{slash}RTC15{slash}SPIQ)MTDI-Pad18)") (class "Default")
      (node (ref "U$1") (pin "18") (pinfunction "(GPIO12/ADC2:5/TOUCH5/RTC15/SPIQ)MTDI_18") (pintype "bidirectional"))
    )
    (net (code "57") (name "unconnected-(U$1-(GPIO13{slash}ADC2:4{slash}TOUCH4{slash}RTC14{slash}SPID{slash}U0CTS)MTCK-Pad20)") (class "Default")
      (node (ref "U$1") (pin "20") (pinfunction "(GPIO13/ADC2:4/TOUCH4/RTC14/SPID/U0CTS)MTCK_20") (pintype "bidirectional"))
    )
    (net (code "58") (name "unconnected-(U$1-(GPIO14{slash}ADC2:6{slash}TOUCH6{slash}RTC16{slash}SPICLK)MTMS-Pad17)") (class "Default")
      (node (ref "U$1") (pin "17") (pinfunction "(GPIO14/ADC2:6/TOUCH6/RTC16/SPICLK)MTMS_17") (pintype "bidirectional"))
    )
    (net (code "59") (name "unconnected-(U$1-(GPIO15{slash}ADC2:3{slash}TOUCH3{slash}RTC13{slash}SPICSO{slash}U0RTS)MTDO-Pad21)") (class "Default")
      (node (ref "U$1") (pin "21") (pinfunction "(GPIO15/ADC2:3/TOUCH3/RTC13/SPICSO/U0RTS)MTDO_21") (pintype "bidirectional"))
    )
    (net (code "60") (name "unconnected-(U$1-(HS1_DATA4)GPIO16-Pad26)") (class "Default")
      (node (ref "U$1") (pin "26") (pinfunction "(HS1_DATA4)GPIO16_26") (pintype "bidirectional"))
    )
    (net (code "61") (name "unconnected-(U$1-(HS1_DATA5)GPIO17-Pad27)") (class "Default")
      (node (ref "U$1") (pin "27") (pinfunction "(HS1_DATA5)GPIO17_27") (pintype "bidirectional"))
    )
    (net (code "62") (name "unconnected-(U$1-(VSPICLK{slash}HS1_DATA7)GPIO18-Pad35)") (class "Default")
      (node (ref "U$1") (pin "35") (pinfunction "(VSPICLK/HS1_DATA7)GPIO18_35") (pintype "bidirectional"))
    )
    (net (code "63") (name "unconnected-(U$1-(VSPID{slash}HS2_DATA3)GPIO20-Pad39)") (class "Default")
      (node (ref "U$1") (pin "39") (pinfunction "(VSPID/HS2_DATA3)GPIO20_39") (pintype "bidirectional"))
    )
    (net (code "64") (name "unconnected-(U$1-(VSPIHD{slash}HS2_CMD)GPIO21-Pad43)") (class "Default")
      (node (ref "U$1") (pin "43") (pinfunction "(VSPIHD/HS2_CMD)GPIO21_43") (pintype "bidirectional"))
    )
    (net (code "65") (name "unconnected-(U$1-(VSPIQ{slash}HS2_DATA2)GPIO19-Pad38)") (class "Default")
      (node (ref "U$1") (pin "38") (pinfunction "(VSPIQ/HS2_DATA2)GPIO19_38") (pintype "bidirectional"))
    )
    (net (code "66") (name "unconnected-(U$1-(VSPIWP{slash}HS2_CLK)GPIO22-Pad40)") (class "Default")
      (node (ref "U$1") (pin "40") (pinfunction "(VSPIWP/HS2_CLK)GPIO22_40") (pintype "bidirectional"))
    )
    (net (code "67") (name "unconnected-(U$1-GPIO23-Pad36)") (class "Default")
      (node (ref "U$1") (pin "36") (pinfunction "GPIO23_36") (pintype "bidirectional"))
    )
    (net (code "68") (name "unconnected-(U$1-SENSOR_CAPN(GPI38{slash}ADC1:2{slash}RTC2)-Pad7)") (class "Default")
      (node (ref "U$1") (pin "7") (pinfunction "SENSOR_CAPN(GPI38/ADC1:2/RTC2)_7") (pintype "bidirectional"))
    )
    (net (code "69") (name "unconnected-(U$1-SENSOR_CAPP(GPI37{slash}ADC1:1{slash}RTC1)-Pad6)") (class "Default")
      (node (ref "U$1") (pin "6") (pinfunction "SENSOR_CAPP(GPI37/ADC1:1/RTC1)_6") (pintype "bidirectional"))
    )
    (net (code "70") (name "unconnected-(U$1-SENSOR_VN(GPI39{slash}ADC1:3{slash}RTC3)-Pad8)") (class "Default")
      (node (ref "U$1") (pin "8") (pinfunction "SENSOR_VN(GPI39/ADC1:3/RTC3)_8") (pintype "bidirectional"))
    )
    (net (code "71") (name "unconnected-(U$1-SENSOR_VP(GPI36{slash}ADC1:0{slash}RTC0)-Pad5)") (class "Default")
      (node (ref "U$1") (pin "5") (pinfunction "SENSOR_VP(GPI36/ADC1:0/RTC0)_5") (pintype "bidirectional"))
    )
    (net (code "72") (name "unconnected-(U$1-VDET_1(GPI34{slash}ADC1:6)-Pad10)") (class "Default")
      (node (ref "U$1") (pin "10") (pinfunction "VDET_1(GPI34/ADC1:6)_10") (pintype "bidirectional"))
    )
    (net (code "73") (name "unconnected-(U$1-VDET_2(GPI35{slash}ADC1:7)-Pad11)") (class "Default")
      (node (ref "U$1") (pin "11") (pinfunction "VDET_2(GPI35/ADC1:7)_11") (pintype "bidirectional"))
    )
    (net (code "74") (name "unconnected-(U3-BP-Pad4)") (class "Default")
      (node (ref "U3") (pin "4") (pinfunction "BP_4") (pintype "input"))
    )
    (net (code "75") (name "unconnected-(U4-CBUS0-Pad18)") (class "Default")
      (node (ref "U4") (pin "18") (pinfunction "CBUS0_18") (pintype "bidirectional"))
    )
    (net (code "76") (name "unconnected-(U4-CBUS1-Pad17)") (class "Default")
      (node (ref "U4") (pin "17") (pinfunction "CBUS1_17") (pintype "bidirectional"))
    )
    (net (code "77") (name "unconnected-(U4-CBUS2-Pad10)") (class "Default")
      (node (ref "U4") (pin "10") (pinfunction "CBUS2_10") (pintype "bidirectional"))
    )
    (net (code "78") (name "unconnected-(U4-CBUS3-Pad19)") (class "Default")
      (node (ref "U4") (pin "19") (pinfunction "CBUS3_19") (pintype "bidirectional"))
    )
    (net (code "79") (name "unconnected-(U4-~{CTS}-Pad9)") (class "Default")
      (node (ref "U4") (pin "9") (pinfunction "~{CTS}_9") (pintype "bidirectional"))
    )
    (net (code "80") (name "unconnected-(U4-~{DCD}-Pad8)") (class "Default")
      (node (ref "U4") (pin "8") (pinfunction "~{DCD}_8") (pintype "bidirectional"))
    )
    (net (code "81") (name "unconnected-(U4-~{DSR}-Pad7)") (class "Default")
      (node (ref "U4") (pin "7") (pinfunction "~{DSR}_7") (pintype "bidirectional"))
    )
    (net (code "82") (name "unconnected-(U4-~{RI}-Pad5)") (class "Default")
      (node (ref "U4") (pin "5") (pinfunction "~{RI}_5") (pintype "bidirectional"))
    )
  )
)
